# power.net
KiCad netlist of a schematic drawn in Altium Designer
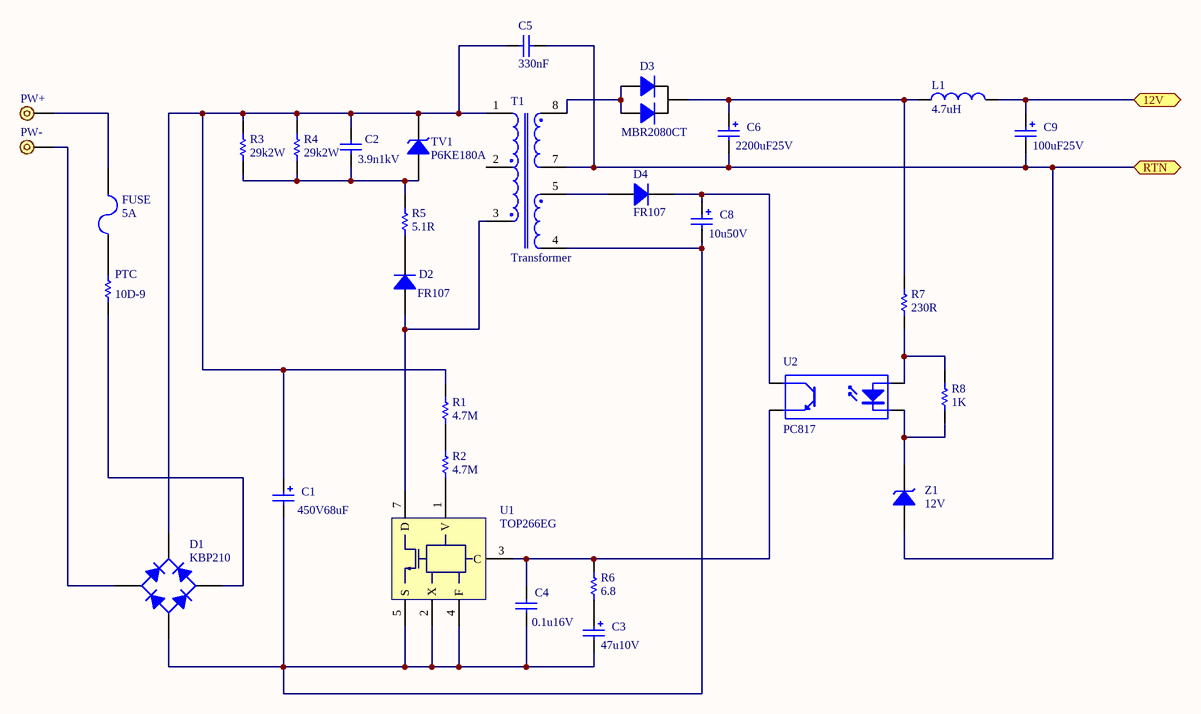
[diagram p0: power.SchDoc]

(export (version "E")
  (design (tool "Eeschema 10.0.6"))
  (components
    (comp (ref "C1")
      (value "450V68uF")
      (footprint "CAP_18x30")
      (description "Polarized Capacitor (Axial)")
      (fields (field (name "PUBLISHER") "Altium Limited"))
      (libsource (lib "magcontrol") (part "Cap Pol2"))
    )
    (comp (ref "C2")
      (value "3.9n1kV")
      (footprint "CAP7")
      (description "Capacitor")
      (fields (field (name "PUBLISHER") "Altium Limited"))
      (libsource (lib "magcontrol") (part "Cap"))
    )
    (comp (ref "C3")
      (value "47u10V")
      (footprint "CAP3")
      (description "Polarized Capacitor (Axial)")
      (fields (field (name "PUBLISHER") "Altium Limited"))
      (libsource (lib "magcontrol") (part "Cap Pol2"))
    )
    (comp (ref "C4")
      (value "0.1u16V")
      (footprint "CAP6")
      (description "Capacitor")
      (fields (field (name "PUBLISHER") "Altium Limited"))
      (libsource (lib "magcontrol") (part "Cap"))
    )
    (comp (ref "C5")
      (value "330nF")
      (footprint "CAP_MKP")
      (description "Capacitor")
      (fields (field (name "PUBLISHER") "Altium Limited"))
      (libsource (lib "magcontrol") (part "Cap"))
    )
    (comp (ref "C6")
      (value "2200uF25V")
      (footprint "CAP_18x30")
      (description "Polarized Capacitor (Axial)")
      (fields (field (name "PUBLISHER") "Altium Limited"))
      (libsource (lib "magcontrol") (part "Cap Pol2"))
    )
    (comp (ref "C8")
      (value "10u50V")
      (footprint "CAP3")
      (description "Polarized Capacitor (Axial)")
      (fields (field (name "PUBLISHER") "Altium Limited"))
      (libsource (lib "magcontrol") (part "Cap Pol2"))
    )
    (comp (ref "C9")
      (value "100uF25V")
      (footprint "CAP3")
      (description "Polarized Capacitor (Axial)")
      (fields (field (name "PUBLISHER") "Altium Limited"))
      (libsource (lib "magcontrol") (part "Cap Pol2"))
    )
    (comp (ref "D1")
      (value "KBP210")
      (footprint "KBP310")
      (description "Single Phase Rectifier Bridge")
      (fields (field (name "PUBLISHER") "Altium Limited"))
      (libsource (lib "magcontrol") (part "KBP310"))
    )
    (comp (ref "D2")
      (value "FR107")
      (footprint "DIO1")
      (description "1 Amp Fast Recovery Rectifier")
      (fields (field (name "PUBLISHER") "Altium Limited"))
      (libsource (lib "tecctrl") (part "Diode"))
    )
    (comp (ref "D3")
      (value "MBR2080CT")
      (footprint "TO247_TO220_SINK")
      (description "Dual Diode TO-247")
      (fields (field (name "PUBLISHER") "Altium Limited"))
      (libsource (lib "tecctrl") (part "Diode2"))
    )
    (comp (ref "D4")
      (value "FR107")
      (footprint "DIO1")
      (description "1 Amp Fast Recovery Rectifier")
      (fields (field (name "PUBLISHER") "Altium Limited"))
      (libsource (lib "tecctrl") (part "Diode"))
    )
    (comp (ref "FUSE")
      (value "5A")
      (footprint "FUSE5X20")
      (description "Fuse")
      (fields (field (name "PUBLISHER") "Altium Limited"))
      (libsource (lib "magcontrol") (part "Fuse 2"))
    )
    (comp (ref "L1")
      (value "4.7uH")
      (footprint "CHOKE")
      (description "Inductor")
      (fields (field (name "PUBLISHER") "Altium Limited"))
      (libsource (lib "magcontrol") (part "Inductor"))
    )
    (comp (ref "PTC")
      (value "10D-9")
      (footprint "PTC")
      (description "Resistor")
      (fields (field (name "PUBLISHER") "Altium Limited"))
      (libsource (lib "magcontrol") (part "Res1"))
    )
    (comp (ref "PW+")
      (value "~")
      (footprint "PAD1")
      (description "Header, 1-Pin")
      (fields (field (name "PUBLISHER") "Altium Limited"))
      (libsource (lib "Miscellaneous Connectors") (part "Header1"))
    )
    (comp (ref "PW-")
      (value "~")
      (footprint "PAD1")
      (description "Header, 1-Pin")
      (fields (field (name "PUBLISHER") "Altium Limited"))
      (libsource (lib "Miscellaneous Connectors") (part "Header1"))
    )
    (comp (ref "R1")
      (value "4.7M")
      (footprint "RES0.25W")
      (description "Resistor")
      (fields (field (name "PUBLISHER") "Altium Limited"))
      (libsource (lib "magcontrol") (part "Res1"))
    )
    (comp (ref "R2")
      (value "4.7M")
      (footprint "RES0.25W")
      (description "Resistor")
      (fields (field (name "PUBLISHER") "Altium Limited"))
      (libsource (lib "magcontrol") (part "Res1"))
    )
    (comp (ref "R3")
      (value "29k2W")
      (footprint "RES2W_H")
      (description "Resistor")
      (fields (field (name "PUBLISHER") "Altium Limited"))
      (libsource (lib "magcontrol") (part "Res1"))
    )
    (comp (ref "R4")
      (value "29k2W")
      (footprint "RES2W_H")
      (description "Resistor")
      (fields (field (name "PUBLISHER") "Altium Limited"))
      (libsource (lib "magcontrol") (part "Res1"))
    )
    (comp (ref "R5")
      (value "5.1R")
      (footprint "RES0.25W")
      (description "Resistor")
      (fields (field (name "PUBLISHER") "Altium Limited"))
      (libsource (lib "magcontrol") (part "Res1"))
    )
    (comp (ref "R6")
      (value "6.8")
      (footprint "RES0.25W")
      (description "Resistor")
      (fields (field (name "PUBLISHER") "Altium Limited"))
      (libsource (lib "magcontrol") (part "Res1"))
    )
    (comp (ref "R7")
      (value "230R")
      (footprint "RES0.25W")
      (description "Resistor")
      (fields (field (name "PUBLISHER") "Altium Limited"))
      (libsource (lib "magcontrol") (part "Res1"))
    )
    (comp (ref "R8")
      (value "1K")
      (footprint "RES0.25W")
      (description "Resistor")
      (fields (field (name "PUBLISHER") "Altium Limited"))
      (libsource (lib "magcontrol") (part "Res1"))
    )
    (comp (ref "T1")
      (value "Transformer")
      (footprint "EER28")
      (fields (field (name "PUBLISHER") "Altium Limited"))
      (libsource (lib "tecctrl") (part "EER28"))
    )
    (comp (ref "TV1")
      (value "P6KE180A")
      (footprint "DIO1")
      (description "Zener Diode")
      (fields (field (name "PUBLISHER") "Altium Limited"))
      (libsource (lib "tecctrl") (part "D Zener"))
    )
    (comp (ref "U1")
      (value "TOP266EG")
      (footprint "eSIP_SINK")
      (description "PI TopSwitch II")
      (libsource (lib "tecctrl") (part "TOP26xEG"))
    )
    (comp (ref "U2")
      (value "PC817")
      (footprint "DIP-4")
      (description "4-Pin Phototransistor Optocoupler")
      (fields (field (name "PUBLISHER") "Altium Limited"))
      (libsource (lib "Miscellaneous Devices") (part "Optoisolator1"))
    )
    (comp (ref "Z1")
      (value "12V")
      (footprint "DIO2")
      (description "Zener Diode")
      (fields (field (name "PUBLISHER") "Altium Limited"))
      (libsource (lib "tecctrl") (part "D Zener"))
    )
  )
  (nets
    (net (code "1") (name "/12V") (class "Default")
      (node (ref "C9") (pin "1") (pinfunction "1_1") (pintype "passive"))
      (node (ref "L1") (pin "2") (pinfunction "2_2") (pintype "passive"))
    )
    (net (code "2") (name "/RTN") (class "Default")
      (node (ref "C5") (pin "2") (pinfunction "2_2") (pintype "passive"))
      (node (ref "C6") (pin "2") (pinfunction "2_2") (pintype "passive"))
      (node (ref "C9") (pin "2") (pinfunction "2_2") (pintype "passive"))
      (node (ref "T1") (pin "7") (pinfunction "7_7") (pintype "passive"))
      (node (ref "Z1") (pin "1") (pinfunction "A_1") (pintype "passive"))
    )
    (net (code "3") (name "Net-(C3-Pad1)") (class "Default")
      (node (ref "C3") (pin "1") (pinfunction "1_1") (pintype "passive"))
      (node (ref "R6") (pin "1") (pinfunction "1_1") (pintype "passive"))
    )
    (net (code "4") (name "Net-(D1-A)") (class "Default")
      (node (ref "C1") (pin "2") (pinfunction "2_2") (pintype "passive"))
      (node (ref "C3") (pin "2") (pinfunction "2_2") (pintype "passive"))
      (node (ref "C4") (pin "2") (pinfunction "2_2") (pintype "passive"))
      (node (ref "C8") (pin "2") (pinfunction "2_2") (pintype "passive"))
      (node (ref "D1") (pin "4") (pinfunction "A_4") (pintype "passive"))
      (node (ref "T1") (pin "4") (pinfunction "4_4") (pintype "passive"))
      (node (ref "U1") (pin "2") (pinfunction "X_2") (pintype "power_in"))
      (node (ref "U1") (pin "4") (pinfunction "F_4") (pintype "power_in"))
      (node (ref "U1") (pin "5") (pinfunction "S_5") (pintype "power_in"))
    )
    (net (code "5") (name "Net-(D1-C-Pad2)") (class "Default")
      (node (ref "D1") (pin "2") (pinfunction "C_2") (pintype "passive"))
      (node (ref "PTC") (pin "2") (pinfunction "2_2") (pintype "passive"))
    )
    (net (code "6") (name "Net-(D1-C-Pad3)") (class "Default")
      (node (ref "D1") (pin "3") (pinfunction "C_3") (pintype "passive"))
      (node (ref "PW-") (pin "1") (pinfunction "1_1") (pintype "passive"))
    )
    (net (code "7") (name "Net-(D1-K)") (class "Default")
      (node (ref "C1") (pin "1") (pinfunction "1_1") (pintype "passive"))
      (node (ref "C2") (pin "1") (pinfunction "1_1") (pintype "passive"))
      (node (ref "C5") (pin "1") (pinfunction "1_1") (pintype "passive"))
      (node (ref "D1") (pin "1") (pinfunction "K_1") (pintype "passive"))
      (node (ref "R1") (pin "2") (pinfunction "2_2") (pintype "passive"))
      (node (ref "R3") (pin "2") (pinfunction "2_2") (pintype "passive"))
      (node (ref "R4") (pin "2") (pinfunction "2_2") (pintype "passive"))
      (node (ref "T1") (pin "1") (pinfunction "1_1") (pintype "passive"))
      (node (ref "TV1") (pin "2") (pinfunction "K_2") (pintype "passive"))
    )
    (net (code "8") (name "Net-(D2-A)") (class "Default")
      (node (ref "D2") (pin "1") (pinfunction "A_1") (pintype "passive"))
      (node (ref "T1") (pin "3") (pinfunction "3_3") (pintype "passive"))
      (node (ref "U1") (pin "7") (pinfunction "D_7") (pintype "power_in"))
    )
    (net (code "9") (name "Net-(D2-K)") (class "Default")
      (node (ref "D2") (pin "2") (pinfunction "K_2") (pintype "passive"))
      (node (ref "R5") (pin "1") (pinfunction "1_1") (pintype "passive"))
    )
    (net (code "10") (name "Net-(D3-A-Pad1)") (class "Default")
      (node (ref "D3") (pin "1") (pinfunction "A_1") (pintype "passive"))
      (node (ref "D3") (pin "3") (pinfunction "A_3") (pintype "passive"))
      (node (ref "T1") (pin "8") (pinfunction "8_8") (pintype "passive"))
    )
    (net (code "11") (name "Net-(D3-K)") (class "Default")
      (node (ref "C6") (pin "1") (pinfunction "1_1") (pintype "passive"))
      (node (ref "D3") (pin "2") (pinfunction "K_2") (pintype "passive"))
      (node (ref "L1") (pin "1") (pinfunction "1_1") (pintype "passive"))
      (node (ref "R7") (pin "2") (pinfunction "2_2") (pintype "passive"))
    )
    (net (code "12") (name "Net-(D4-A)") (class "Default")
      (node (ref "D4") (pin "1") (pinfunction "A_1") (pintype "passive"))
      (node (ref "T1") (pin "5") (pinfunction "5_5") (pintype "passive"))
    )
    (net (code "13") (name "Net-(D4-K)") (class "Default")
      (node (ref "C8") (pin "1") (pinfunction "1_1") (pintype "passive"))
      (node (ref "D4") (pin "2") (pinfunction "K_2") (pintype "passive"))
      (node (ref "U2") (pin "4") (pinfunction "C_4") (pintype "passive"))
    )
    (net (code "14") (name "Net-(FUSE-Pad1)") (class "Default")
      (node (ref "FUSE") (pin "1") (pinfunction "1_1") (pintype "passive"))
      (node (ref "PW+") (pin "1") (pinfunction "1_1") (pintype "passive"))
    )
    (net (code "15") (name "Net-(FUSE-Pad2)") (class "Default")
      (node (ref "FUSE") (pin "2") (pinfunction "2_2") (pintype "passive"))
      (node (ref "PTC") (pin "1") (pinfunction "1_1") (pintype "passive"))
    )
    (net (code "16") (name "Net-(R1-Pad1)") (class "Default")
      (node (ref "R1") (pin "1") (pinfunction "1_1") (pintype "passive"))
      (node (ref "R2") (pin "2") (pinfunction "2_2") (pintype "passive"))
    )
    (net (code "17") (name "Net-(TV1-A)") (class "Default")
      (node (ref "C2") (pin "2") (pinfunction "2_2") (pintype "passive"))
      (node (ref "R3") (pin "1") (pinfunction "1_1") (pintype "passive"))
      (node (ref "R4") (pin "1") (pinfunction "1_1") (pintype "passive"))
      (node (ref "R5") (pin "2") (pinfunction "2_2") (pintype "passive"))
      (node (ref "TV1") (pin "1") (pinfunction "A_1") (pintype "passive"))
    )
    (net (code "18") (name "Net-(U1-C)") (class "Default")
      (node (ref "C4") (pin "1") (pinfunction "1_1") (pintype "passive"))
      (node (ref "R6") (pin "2") (pinfunction "2_2") (pintype "passive"))
      (node (ref "U1") (pin "3") (pinfunction "C_3") (pintype "power_in"))
      (node (ref "U2") (pin "3") (pinfunction "E_3") (pintype "passive"))
    )
    (net (code "19") (name "Net-(U1-V)") (class "Default")
      (node (ref "R2") (pin "1") (pinfunction "1_1") (pintype "passive"))
      (node (ref "U1") (pin "1") (pinfunction "V_1") (pintype "power_in"))
    )
    (net (code "20") (name "Net-(U2-A)") (class "Default")
      (node (ref "R7") (pin "1") (pinfunction "1_1") (pintype "passive"))
      (node (ref "R8") (pin "2") (pinfunction "2_2") (pintype "passive"))
      (node (ref "U2") (pin "1") (pinfunction "A_1") (pintype "passive"))
    )
    (net (code "21") (name "Net-(U2-K)") (class "Default")
      (node (ref "R8") (pin "1") (pinfunction "1_1") (pintype "passive"))
      (node (ref "U2") (pin "2") (pinfunction "K_2") (pintype "passive"))
      (node (ref "Z1") (pin "2") (pinfunction "K_2") (pintype "passive"))
    )
    (net (code "22") (name "unconnected-(T1-Pad2)") (class "Default")
      (node (ref "T1") (pin "2") (pinfunction "2_2") (pintype "passive"))
    )
  )
)
